# McPiFace-MiniOled-V1.net
KiCad netlist of a schematic drawn in EAGLE
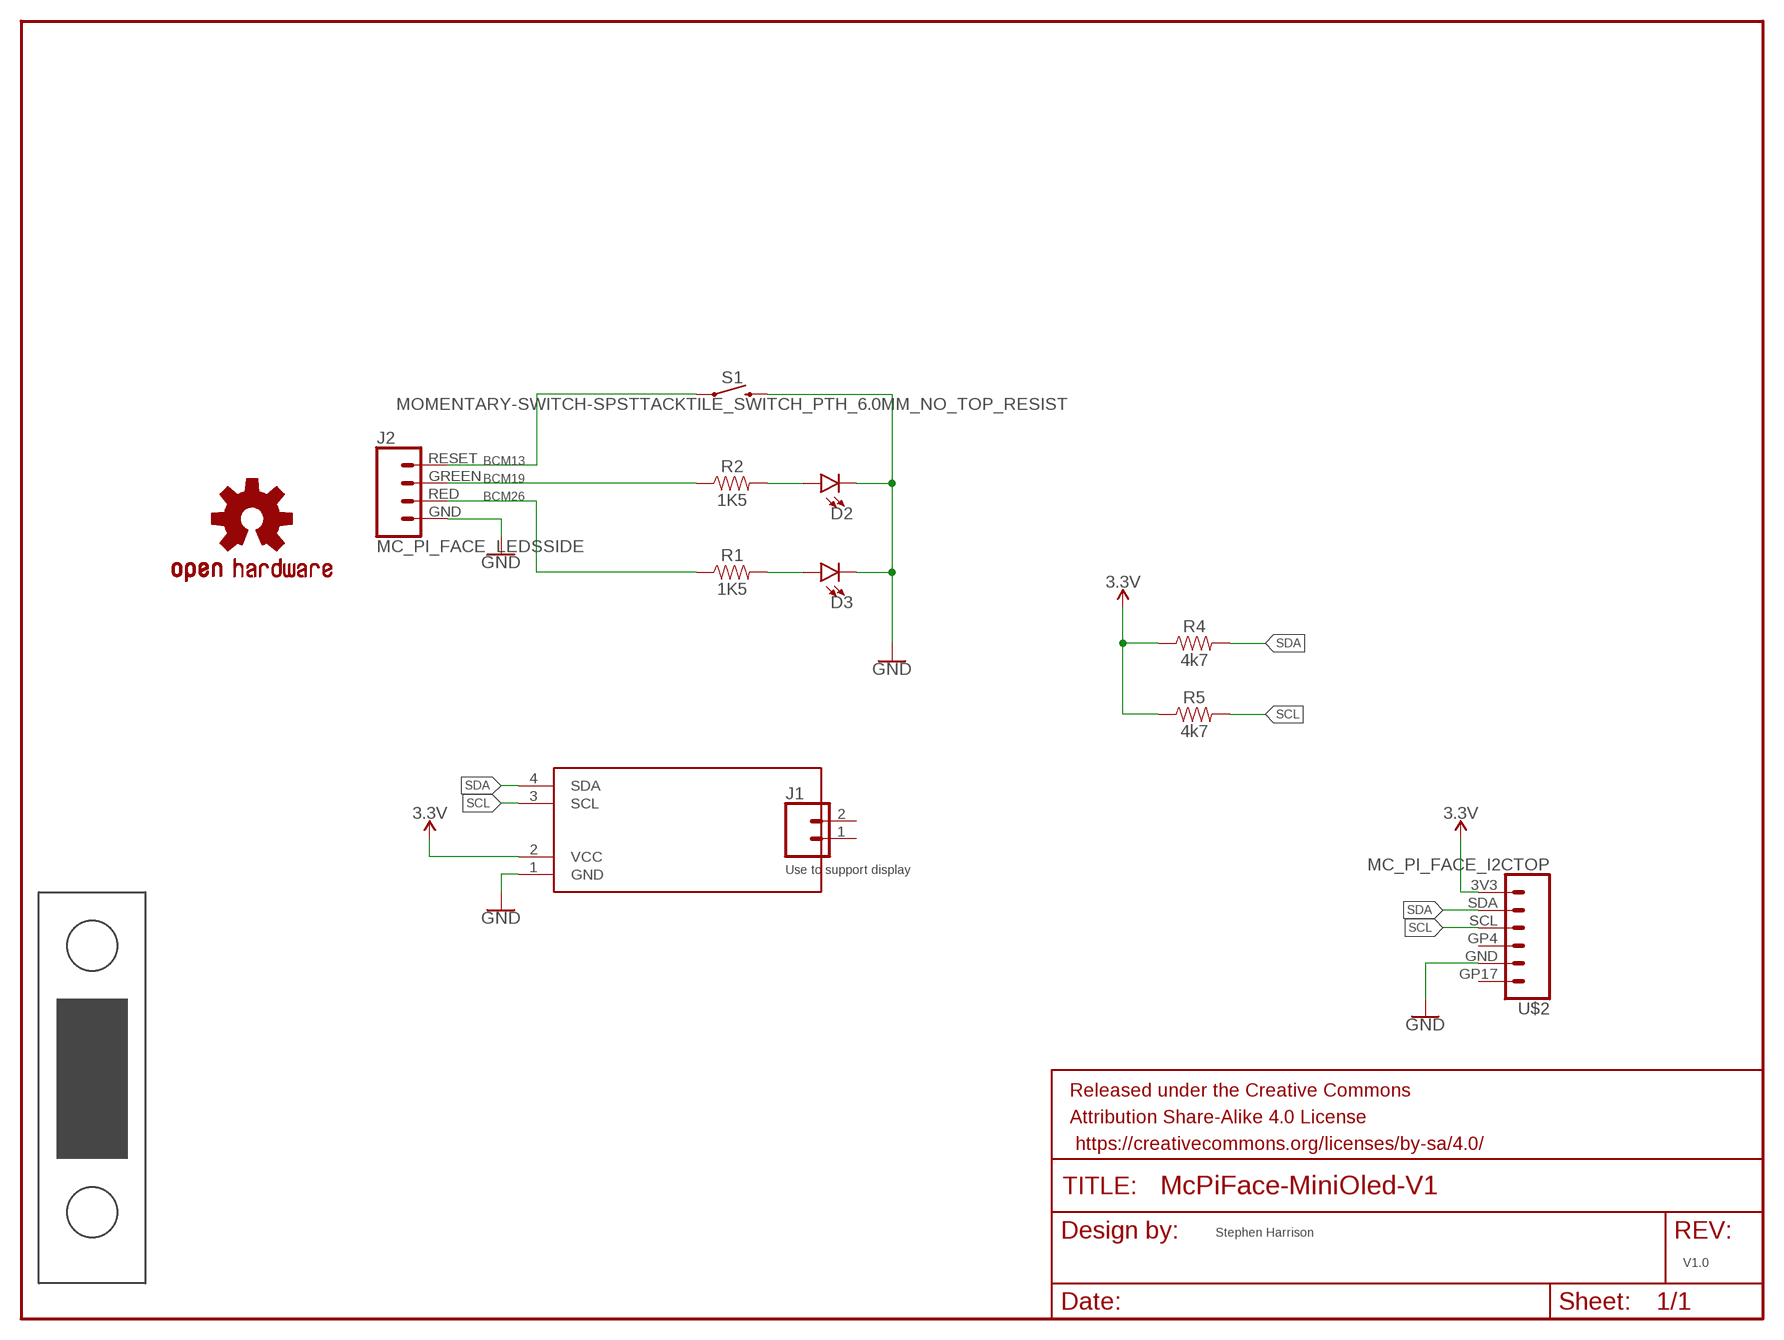
[diagram p0: schematic, sheet 1]

(export (version "E")
  (design (tool "Eeschema 10.0.6"))
  (components
    (comp (ref "D2")
      (value "LEDLED-1206-BOTTOM-2.0MM-GREEN")
      (footprint "eagle-import:LED-1206-BOTTOM-2.0MM")
      (libsource (lib "eagle-import") (part "LEDLED-1206-BOTTOM-2.0MM-GREEN"))
    )
    (comp (ref "D3")
      (value "LEDLED-1206-BOTTOM-2.0MM-RED")
      (footprint "eagle-import:LED-1206-BOTTOM-2.0MM")
      (libsource (lib "eagle-import") (part "LEDLED-1206-BOTTOM-2.0MM-RED"))
    )
    (comp (ref "DISPLAY")
      (value "DISPLAY0.91_INCH_DISPLAY")
      (footprint "eagle-import:I2C_DISPLAY_0.91_INCH")
      (libsource (lib "eagle-import") (part "DISPLAY0.91_INCH_DISPLAY"))
    )
    (comp (ref "FRAME1")
      (value "FRAME-LETTER")
      (footprint "eagle-import:CREATIVE_COMMONS")
      (libsource (lib "eagle-import") (part "FRAME-LETTER"))
    )
    (comp (ref "J1")
      (value "CONN_021X02_NO_SILK")
      (footprint "eagle-import:1X02_NO_SILK")
      (libsource (lib "eagle-import") (part "CONN_021X02_NO_SILK"))
    )
    (comp (ref "J2")
      (value "MC_PI_FACE_LEDSSIDE")
      (footprint "eagle-import:JST-4-SH-1.0MM-SIDE")
      (fields (field (name "MFG") "SM04B-SRSS-TB(LF)(SN)"))
      (libsource (lib "eagle-import") (part "MC_PI_FACE_LEDSSIDE"))
    )
    (comp (ref "LOGO1")
      (value "OSHW-LOGOL")
      (footprint "eagle-import:OSHW-LOGO-L")
      (libsource (lib "eagle-import") (part "OSHW-LOGOL"))
    )
    (comp (ref "R1")
      (value "1K5")
      (footprint "eagle-import:0805")
      (libsource (lib "eagle-import") (part "RESISTOR0805"))
    )
    (comp (ref "R2")
      (value "1K5")
      (footprint "eagle-import:0805")
      (libsource (lib "eagle-import") (part "RESISTOR0805"))
    )
    (comp (ref "R4")
      (value "4k7")
      (footprint "eagle-import:0805")
      (libsource (lib "eagle-import") (part "RESISTOR0805"))
    )
    (comp (ref "R5")
      (value "4k7")
      (footprint "eagle-import:0805")
      (libsource (lib "eagle-import") (part "RESISTOR0805"))
    )
    (comp (ref "S1")
      (value "MOMENTARY-SWITCH-SPSTTACKTILE_SWITCH_PTH_6.0MM_NO_TOP_RESIST")
      (footprint "eagle-import:TACTILE_SWITCH_PTH_6.0MM_NO_TOP_RESIST")
      (libsource (lib "eagle-import") (part "MOMENTARY-SWITCH-SPSTTACKTILE_SWITCH_PTH_6.0MM_NO_TOP_RESIST"))
    )
    (comp (ref "U$1")
      (value "MC_PI_FACE_JOINT")
      (footprint "eagle-import:MC_PI_FACE_JOINT")
      (libsource (lib "eagle-import") (part "MC_PI_FACE_JOINT"))
    )
    (comp (ref "U$2")
      (value "MC_PI_FACE_I2CTOP")
      (footprint "eagle-import:JST-6-SH-1.0MM-TOP")
      (libsource (lib "eagle-import") (part "MC_PI_FACE_I2CTOP"))
    )
  )
  (nets
    (net (code "1") (name "/BCM13") (class "Default")
      (node (ref "J2") (pin "RESET") (pinfunction "RESET_RESET") (pintype "passive"))
      (node (ref "S1") (pin "1") (pinfunction "1_1") (pintype "passive"))
    )
    (net (code "2") (name "/BCM19") (class "Default")
      (node (ref "J2") (pin "GREEN") (pinfunction "GREEN_GREEN") (pintype "passive"))
      (node (ref "R2") (pin "1") (pinfunction "1_1") (pintype "passive"))
    )
    (net (code "3") (name "/BCM26") (class "Default")
      (node (ref "J2") (pin "RED") (pinfunction "RED_RED") (pintype "passive"))
      (node (ref "R1") (pin "1") (pinfunction "1_1") (pintype "passive"))
    )
    (net (code "4") (name "3.3V") (class "Default")
      (node (ref "DISPLAY") (pin "2") (pinfunction "VCC_2") (pintype "power_in"))
      (node (ref "R4") (pin "1") (pinfunction "1_1") (pintype "passive"))
      (node (ref "R5") (pin "1") (pinfunction "1_1") (pintype "passive"))
      (node (ref "U$2") (pin "3V3") (pinfunction "3V3_3V3") (pintype "power_in"))
    )
    (net (code "5") (name "GND") (class "Default")
      (node (ref "D2") (pin "C") (pinfunction "C_C") (pintype "passive"))
      (node (ref "D3") (pin "C") (pinfunction "C_C") (pintype "passive"))
      (node (ref "DISPLAY") (pin "1") (pinfunction "GND_1") (pintype "power_in"))
      (node (ref "J2") (pin "GND") (pinfunction "GND_GND") (pintype "power_in"))
      (node (ref "S1") (pin "3") (pinfunction "2_3") (pintype "passive"))
      (node (ref "U$2") (pin "GND") (pinfunction "GND_GND") (pintype "power_in"))
    )
    (net (code "6") (name "Net-(D2-PadA)") (class "Default")
      (node (ref "D2") (pin "A") (pinfunction "A_A") (pintype "passive"))
      (node (ref "R2") (pin "2") (pinfunction "2_2") (pintype "passive"))
    )
    (net (code "7") (name "Net-(D3-PadA)") (class "Default")
      (node (ref "D3") (pin "A") (pinfunction "A_A") (pintype "passive"))
      (node (ref "R1") (pin "2") (pinfunction "2_2") (pintype "passive"))
    )
    (net (code "8") (name "SCL") (class "Default")
      (node (ref "DISPLAY") (pin "3") (pinfunction "SCL_3") (pintype "bidirectional"))
      (node (ref "R5") (pin "2") (pinfunction "2_2") (pintype "passive"))
      (node (ref "U$2") (pin "SCL") (pinfunction "SCL_SCL") (pintype "bidirectional"))
    )
    (net (code "9") (name "SDA") (class "Default")
      (node (ref "DISPLAY") (pin "4") (pinfunction "SDA_4") (pintype "bidirectional"))
      (node (ref "R4") (pin "2") (pinfunction "2_2") (pintype "passive"))
      (node (ref "U$2") (pin "SDA") (pinfunction "SDA_SDA") (pintype "bidirectional"))
    )
    (net (code "10") (name "unconnected-(J1-Pad1)") (class "Default")
      (node (ref "J1") (pin "1") (pinfunction "1_1") (pintype "passive"))
    )
    (net (code "11") (name "unconnected-(J1-Pad2)") (class "Default")
      (node (ref "J1") (pin "2") (pinfunction "2_2") (pintype "passive"))
    )
    (net (code "12") (name "unconnected-(U$2-PadGP4)") (class "Default")
      (node (ref "U$2") (pin "GP4") (pinfunction "GP4_GP4") (pintype "bidirectional"))
    )
    (net (code "13") (name "unconnected-(U$2-PadGP17)") (class "Default")
      (node (ref "U$2") (pin "GP17") (pinfunction "GP17_GP17") (pintype "bidirectional"))
    )
  )
)
